# schematic.net
KiCad netlist of a schematic drawn in EAGLE
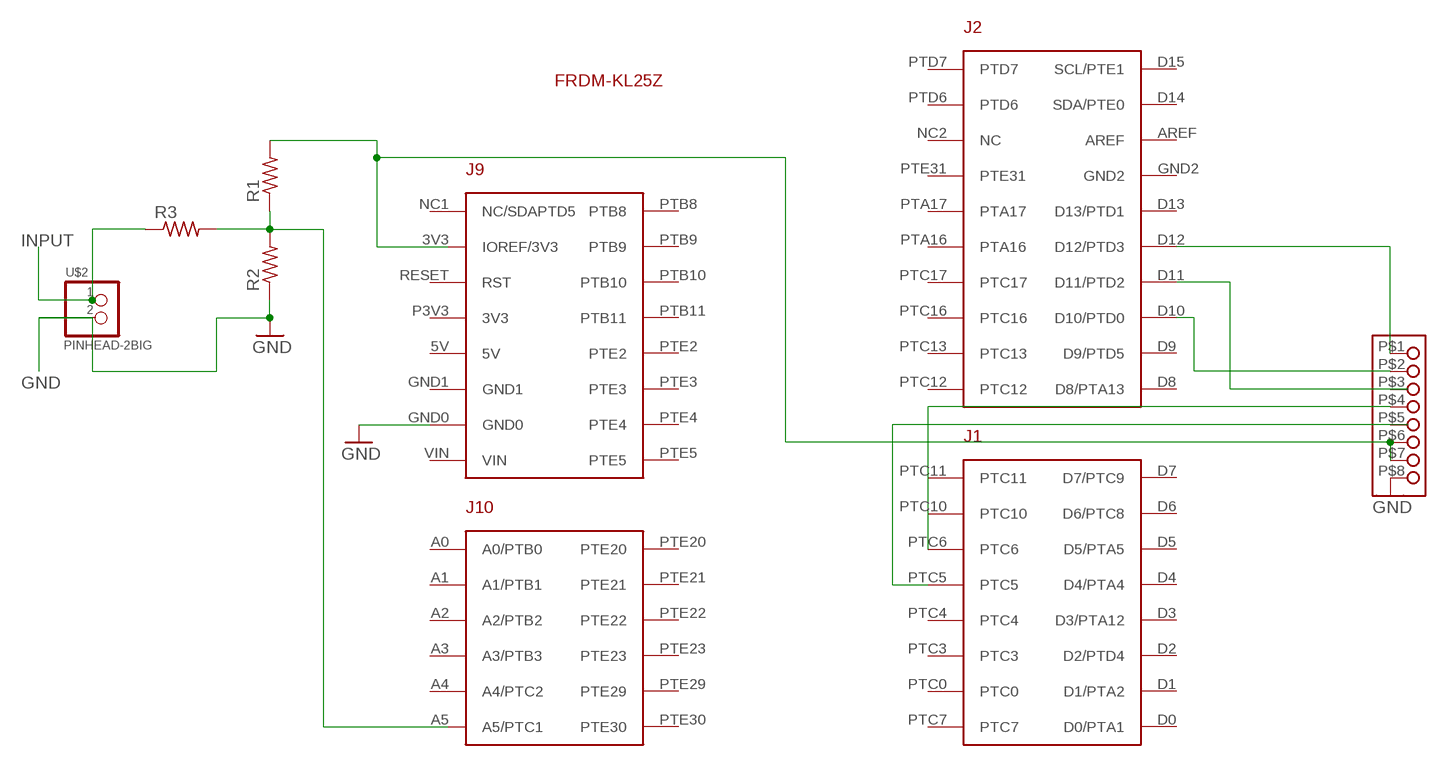
[diagram p0: schematic, sheet 1]

(export (version "E")
  (design (tool "Eeschema 10.0.6"))
  (components
    (comp (ref "FRDM1")
      (value "FRDM-KL25ZARDUINO")
      (footprint "eagle-import:FRDM-KL25Z")
      (libsource (lib "eagle-import") (part "FRDM-KL25ZARDUINO"))
    )
    (comp (ref "R1")
      (value "R-US_0204/5")
      (footprint "eagle-import:0204_5")
      (libsource (lib "eagle-import") (part "R-US_0204/5"))
    )
    (comp (ref "R2")
      (value "R-US_0204/5")
      (footprint "eagle-import:0204_5")
      (libsource (lib "eagle-import") (part "R-US_0204/5"))
    )
    (comp (ref "R3")
      (value "R-US_0204/5")
      (footprint "eagle-import:0204_5")
      (libsource (lib "eagle-import") (part "R-US_0204/5"))
    )
    (comp (ref "U$1")
      (value "PINHEAD-8")
      (footprint "eagle-import:PTH-8-1MM")
      (libsource (lib "eagle-import") (part "PINHEAD-8"))
    )
    (comp (ref "U$2")
      (value "PINHEAD-2BIG")
      (footprint "eagle-import:BIGPIN-2")
      (libsource (lib "eagle-import") (part "PINHEAD-2BIG"))
    )
  )
  (nets
    (net (code "1") (name "/INPUT") (class "Default")
      (node (ref "R3") (pin "1") (pinfunction "1_1") (pintype "passive"))
      (node (ref "U$2") (pin "P$1") (pinfunction "1_P$1") (pintype "bidirectional"))
    )
    (net (code "2") (name "GND") (class "Default")
      (node (ref "FRDM1") (pin "GND0") (pinfunction "GND0_GND0") (pintype "bidirectional"))
      (node (ref "R2") (pin "1") (pinfunction "1_1") (pintype "passive"))
      (node (ref "U$1") (pin "P$8") (pinfunction "P$8_P$8") (pintype "bidirectional"))
      (node (ref "U$2") (pin "P$2") (pinfunction "2_P$2") (pintype "bidirectional"))
    )
    (net (code "3") (name "Net-(FRDM1-D10{slash}PTD0)") (class "Default")
      (node (ref "FRDM1") (pin "D10") (pinfunction "D10/PTD0_D10") (pintype "bidirectional"))
      (node (ref "U$1") (pin "P$2") (pinfunction "P$2_P$2") (pintype "bidirectional"))
    )
    (net (code "4") (name "Net-(FRDM1-D12{slash}PTD3)") (class "Default")
      (node (ref "FRDM1") (pin "D12") (pinfunction "D12/PTD3_D12") (pintype "bidirectional"))
      (node (ref "U$1") (pin "P$1") (pinfunction "P$1_P$1") (pintype "bidirectional"))
    )
    (net (code "5") (name "Net-(FRDM1-PadPTC6)") (class "Default")
      (node (ref "FRDM1") (pin "PTC6") (pinfunction "PTC6_PTC6") (pintype "bidirectional"))
      (node (ref "U$1") (pin "P$4") (pinfunction "P$4_P$4") (pintype "bidirectional"))
    )
    (net (code "6") (name "Net-(R1-Pad1)") (class "Default")
      (node (ref "R1") (pin "1") (pinfunction "1_1") (pintype "passive"))
      (node (ref "R2") (pin "2") (pinfunction "2_2") (pintype "passive"))
      (node (ref "R3") (pin "2") (pinfunction "2_2") (pintype "passive"))
    )
    (net (code "7") (name "Net-(R1-Pad2)") (class "Default")
      (node (ref "R1") (pin "2") (pinfunction "2_2") (pintype "passive"))
      (node (ref "U$1") (pin "P$6") (pinfunction "P$6_P$6") (pintype "bidirectional"))
      (node (ref "U$1") (pin "P$7") (pinfunction "P$7_P$7") (pintype "bidirectional"))
    )
    (net (code "8") (name "unconnected-(FRDM1-3V3-PadP3V3)") (class "Default")
      (node (ref "FRDM1") (pin "P3V3") (pinfunction "3V3_P3V3") (pintype "bidirectional"))
    )
    (net (code "9") (name "unconnected-(FRDM1-A0{slash}PTB0-PadA0)") (class "Default")
      (node (ref "FRDM1") (pin "A0") (pinfunction "A0/PTB0_A0") (pintype "bidirectional"))
    )
    (net (code "10") (name "unconnected-(FRDM1-A1{slash}PTB1-PadA1)") (class "Default")
      (node (ref "FRDM1") (pin "A1") (pinfunction "A1/PTB1_A1") (pintype "bidirectional"))
    )
    (net (code "11") (name "unconnected-(FRDM1-A2{slash}PTB2-PadA2)") (class "Default")
      (node (ref "FRDM1") (pin "A2") (pinfunction "A2/PTB2_A2") (pintype "bidirectional"))
    )
    (net (code "12") (name "unconnected-(FRDM1-A3{slash}PTB3-PadA3)") (class "Default")
      (node (ref "FRDM1") (pin "A3") (pinfunction "A3/PTB3_A3") (pintype "bidirectional"))
    )
    (net (code "13") (name "unconnected-(FRDM1-A4{slash}PTC2-PadA4)") (class "Default")
      (node (ref "FRDM1") (pin "A4") (pinfunction "A4/PTC2_A4") (pintype "bidirectional"))
    )
    (net (code "14") (name "unconnected-(FRDM1-A5{slash}PTC1-PadA5)") (class "Default")
      (node (ref "FRDM1") (pin "A5") (pinfunction "A5/PTC1_A5") (pintype "bidirectional"))
    )
    (net (code "15") (name "unconnected-(FRDM1-D0{slash}PTA1-PadD0)") (class "Default")
      (node (ref "FRDM1") (pin "D0") (pinfunction "D0/PTA1_D0") (pintype "bidirectional"))
    )
    (net (code "16") (name "unconnected-(FRDM1-D1{slash}PTA2-PadD1)") (class "Default")
      (node (ref "FRDM1") (pin "D1") (pinfunction "D1/PTA2_D1") (pintype "bidirectional"))
    )
    (net (code "17") (name "unconnected-(FRDM1-D2{slash}PTD4-PadD2)") (class "Default")
      (node (ref "FRDM1") (pin "D2") (pinfunction "D2/PTD4_D2") (pintype "bidirectional"))
    )
    (net (code "18") (name "unconnected-(FRDM1-D3{slash}PTA12-PadD3)") (class "Default")
      (node (ref "FRDM1") (pin "D3") (pinfunction "D3/PTA12_D3") (pintype "bidirectional"))
    )
    (net (code "19") (name "unconnected-(FRDM1-D4{slash}PTA4-PadD4)") (class "Default")
      (node (ref "FRDM1") (pin "D4") (pinfunction "D4/PTA4_D4") (pintype "bidirectional"))
    )
    (net (code "20") (name "unconnected-(FRDM1-D5{slash}PTA5-PadD5)") (class "Default")
      (node (ref "FRDM1") (pin "D5") (pinfunction "D5/PTA5_D5") (pintype "bidirectional"))
    )
    (net (code "21") (name "unconnected-(FRDM1-D6{slash}PTC8-PadD6)") (class "Default")
      (node (ref "FRDM1") (pin "D6") (pinfunction "D6/PTC8_D6") (pintype "bidirectional"))
    )
    (net (code "22") (name "unconnected-(FRDM1-D7{slash}PTC9-PadD7)") (class "Default")
      (node (ref "FRDM1") (pin "D7") (pinfunction "D7/PTC9_D7") (pintype "bidirectional"))
    )
    (net (code "23") (name "unconnected-(FRDM1-D8{slash}PTA13-PadD8)") (class "Default")
      (node (ref "FRDM1") (pin "D8") (pinfunction "D8/PTA13_D8") (pintype "bidirectional"))
    )
    (net (code "24") (name "unconnected-(FRDM1-D9{slash}PTD5-PadD9)") (class "Default")
      (node (ref "FRDM1") (pin "D9") (pinfunction "D9/PTD5_D9") (pintype "bidirectional"))
    )
    (net (code "25") (name "unconnected-(FRDM1-D11{slash}PTD2-PadD11)") (class "Default")
      (node (ref "FRDM1") (pin "D11") (pinfunction "D11/PTD2_D11") (pintype "bidirectional"))
    )
    (net (code "26") (name "unconnected-(FRDM1-D13{slash}PTD1-PadD13)") (class "Default")
      (node (ref "FRDM1") (pin "D13") (pinfunction "D13/PTD1_D13") (pintype "bidirectional"))
    )
    (net (code "27") (name "unconnected-(FRDM1-IOREF{slash}3V3-Pad3V3)") (class "Default")
      (node (ref "FRDM1") (pin "3V3") (pinfunction "IOREF/3V3_3V3") (pintype "bidirectional"))
    )
    (net (code "28") (name "unconnected-(FRDM1-NC-PadNC2)") (class "Default")
      (node (ref "FRDM1") (pin "NC2") (pinfunction "NC_NC2") (pintype "bidirectional"))
    )
    (net (code "29") (name "unconnected-(FRDM1-NC{slash}SDAPTD5-PadNC1)") (class "Default")
      (node (ref "FRDM1") (pin "NC1") (pinfunction "NC/SDAPTD5_NC1") (pintype "bidirectional"))
    )
    (net (code "30") (name "unconnected-(FRDM1-Pad5V)") (class "Default")
      (node (ref "FRDM1") (pin "5V") (pinfunction "5V_5V") (pintype "bidirectional"))
    )
    (net (code "31") (name "unconnected-(FRDM1-PadAREF)") (class "Default")
      (node (ref "FRDM1") (pin "AREF") (pinfunction "AREF_AREF") (pintype "bidirectional"))
    )
    (net (code "32") (name "unconnected-(FRDM1-PadGND1)") (class "Default")
      (node (ref "FRDM1") (pin "GND1") (pinfunction "GND1_GND1") (pintype "bidirectional"))
    )
    (net (code "33") (name "unconnected-(FRDM1-PadGND2)") (class "Default")
      (node (ref "FRDM1") (pin "GND2") (pinfunction "GND2_GND2") (pintype "bidirectional"))
    )
    (net (code "34") (name "unconnected-(FRDM1-PadPTA16)") (class "Default")
      (node (ref "FRDM1") (pin "PTA16") (pinfunction "PTA16_PTA16") (pintype "bidirectional"))
    )
    (net (code "35") (name "unconnected-(FRDM1-PadPTA17)") (class "Default")
      (node (ref "FRDM1") (pin "PTA17") (pinfunction "PTA17_PTA17") (pintype "bidirectional"))
    )
    (net (code "36") (name "unconnected-(FRDM1-PadPTB8)") (class "Default")
      (node (ref "FRDM1") (pin "PTB8") (pinfunction "PTB8_PTB8") (pintype "bidirectional"))
    )
    (net (code "37") (name "unconnected-(FRDM1-PadPTB9)") (class "Default")
      (node (ref "FRDM1") (pin "PTB9") (pinfunction "PTB9_PTB9") (pintype "bidirectional"))
    )
    (net (code "38") (name "unconnected-(FRDM1-PadPTB10)") (class "Default")
      (node (ref "FRDM1") (pin "PTB10") (pinfunction "PTB10_PTB10") (pintype "bidirectional"))
    )
    (net (code "39") (name "unconnected-(FRDM1-PadPTB11)") (class "Default")
      (node (ref "FRDM1") (pin "PTB11") (pinfunction "PTB11_PTB11") (pintype "bidirectional"))
    )
    (net (code "40") (name "unconnected-(FRDM1-PadPTC0)") (class "Default")
      (node (ref "FRDM1") (pin "PTC0") (pinfunction "PTC0_PTC0") (pintype "bidirectional"))
    )
    (net (code "41") (name "unconnected-(FRDM1-PadPTC3)") (class "Default")
      (node (ref "FRDM1") (pin "PTC3") (pinfunction "PTC3_PTC3") (pintype "bidirectional"))
    )
    (net (code "42") (name "unconnected-(FRDM1-PadPTC4)") (class "Default")
      (node (ref "FRDM1") (pin "PTC4") (pinfunction "PTC4_PTC4") (pintype "bidirectional"))
    )
    (net (code "43") (name "unconnected-(FRDM1-PadPTC5)") (class "Default")
      (node (ref "FRDM1") (pin "PTC5") (pinfunction "PTC5_PTC5") (pintype "bidirectional"))
    )
    (net (code "44") (name "unconnected-(FRDM1-PadPTC7)") (class "Default")
      (node (ref "FRDM1") (pin "PTC7") (pinfunction "PTC7_PTC7") (pintype "bidirectional"))
    )
    (net (code "45") (name "unconnected-(FRDM1-PadPTC10)") (class "Default")
      (node (ref "FRDM1") (pin "PTC10") (pinfunction "PTC10_PTC10") (pintype "bidirectional"))
    )
    (net (code "46") (name "unconnected-(FRDM1-PadPTC11)") (class "Default")
      (node (ref "FRDM1") (pin "PTC11") (pinfunction "PTC11_PTC11") (pintype "bidirectional"))
    )
    (net (code "47") (name "unconnected-(FRDM1-PadPTC12)") (class "Default")
      (node (ref "FRDM1") (pin "PTC12") (pinfunction "PTC12_PTC12") (pintype "bidirectional"))
    )
    (net (code "48") (name "unconnected-(FRDM1-PadPTC13)") (class "Default")
      (node (ref "FRDM1") (pin "PTC13") (pinfunction "PTC13_PTC13") (pintype "bidirectional"))
    )
    (net (code "49") (name "unconnected-(FRDM1-PadPTC16)") (class "Default")
      (node (ref "FRDM1") (pin "PTC16") (pinfunction "PTC16_PTC16") (pintype "bidirectional"))
    )
    (net (code "50") (name "unconnected-(FRDM1-PadPTC17)") (class "Default")
      (node (ref "FRDM1") (pin "PTC17") (pinfunction "PTC17_PTC17") (pintype "bidirectional"))
    )
    (net (code "51") (name "unconnected-(FRDM1-PadPTD6)") (class "Default")
      (node (ref "FRDM1") (pin "PTD6") (pinfunction "PTD6_PTD6") (pintype "bidirectional"))
    )
    (net (code "52") (name "unconnected-(FRDM1-PadPTD7)") (class "Default")
      (node (ref "FRDM1") (pin "PTD7") (pinfunction "PTD7_PTD7") (pintype "bidirectional"))
    )
    (net (code "53") (name "unconnected-(FRDM1-PadPTE2)") (class "Default")
      (node (ref "FRDM1") (pin "PTE2") (pinfunction "PTE2_PTE2") (pintype "bidirectional"))
    )
    (net (code "54") (name "unconnected-(FRDM1-PadPTE3)") (class "Default")
      (node (ref "FRDM1") (pin "PTE3") (pinfunction "PTE3_PTE3") (pintype "bidirectional"))
    )
    (net (code "55") (name "unconnected-(FRDM1-PadPTE4)") (class "Default")
      (node (ref "FRDM1") (pin "PTE4") (pinfunction "PTE4_PTE4") (pintype "bidirectional"))
    )
    (net (code "56") (name "unconnected-(FRDM1-PadPTE5)") (class "Default")
      (node (ref "FRDM1") (pin "PTE5") (pinfunction "PTE5_PTE5") (pintype "bidirectional"))
    )
    (net (code "57") (name "unconnected-(FRDM1-PadPTE20)") (class "Default")
      (node (ref "FRDM1") (pin "PTE20") (pinfunction "PTE20_PTE20") (pintype "bidirectional"))
    )
    (net (code "58") (name "unconnected-(FRDM1-PadPTE21)") (class "Default")
      (node (ref "FRDM1") (pin "PTE21") (pinfunction "PTE21_PTE21") (pintype "bidirectional"))
    )
    (net (code "59") (name "unconnected-(FRDM1-PadPTE22)") (class "Default")
      (node (ref "FRDM1") (pin "PTE22") (pinfunction "PTE22_PTE22") (pintype "bidirectional"))
    )
    (net (code "60") (name "unconnected-(FRDM1-PadPTE23)") (class "Default")
      (node (ref "FRDM1") (pin "PTE23") (pinfunction "PTE23_PTE23") (pintype "bidirectional"))
    )
    (net (code "61") (name "unconnected-(FRDM1-PadPTE29)") (class "Default")
      (node (ref "FRDM1") (pin "PTE29") (pinfunction "PTE29_PTE29") (pintype "bidirectional"))
    )
    (net (code "62") (name "unconnected-(FRDM1-PadPTE30)") (class "Default")
      (node (ref "FRDM1") (pin "PTE30") (pinfunction "PTE30_PTE30") (pintype "bidirectional"))
    )
    (net (code "63") (name "unconnected-(FRDM1-PadPTE31)") (class "Default")
      (node (ref "FRDM1") (pin "PTE31") (pinfunction "PTE31_PTE31") (pintype "bidirectional"))
    )
    (net (code "64") (name "unconnected-(FRDM1-PadVIN)") (class "Default")
      (node (ref "FRDM1") (pin "VIN") (pinfunction "VIN_VIN") (pintype "bidirectional"))
    )
    (net (code "65") (name "unconnected-(FRDM1-RST-PadRESET)") (class "Default")
      (node (ref "FRDM1") (pin "RESET") (pinfunction "RST_RESET") (pintype "bidirectional"))
    )
    (net (code "66") (name "unconnected-(FRDM1-SCL{slash}PTE1-PadD15)") (class "Default")
      (node (ref "FRDM1") (pin "D15") (pinfunction "SCL/PTE1_D15") (pintype "bidirectional"))
    )
    (net (code "67") (name "unconnected-(FRDM1-SDA{slash}PTE0-PadD14)") (class "Default")
      (node (ref "FRDM1") (pin "D14") (pinfunction "SDA/PTE0_D14") (pintype "bidirectional"))
    )
    (net (code "68") (name "unconnected-(U$1-PadP$3)") (class "Default")
      (node (ref "U$1") (pin "P$3") (pinfunction "P$3_P$3") (pintype "bidirectional"))
    )
    (net (code "69") (name "unconnected-(U$1-PadP$5)") (class "Default")
      (node (ref "U$1") (pin "P$5") (pinfunction "P$5_P$5") (pintype "bidirectional"))
    )
  )
)
